# pcb.net
KiCad netlist of a schematic drawn in EAGLE
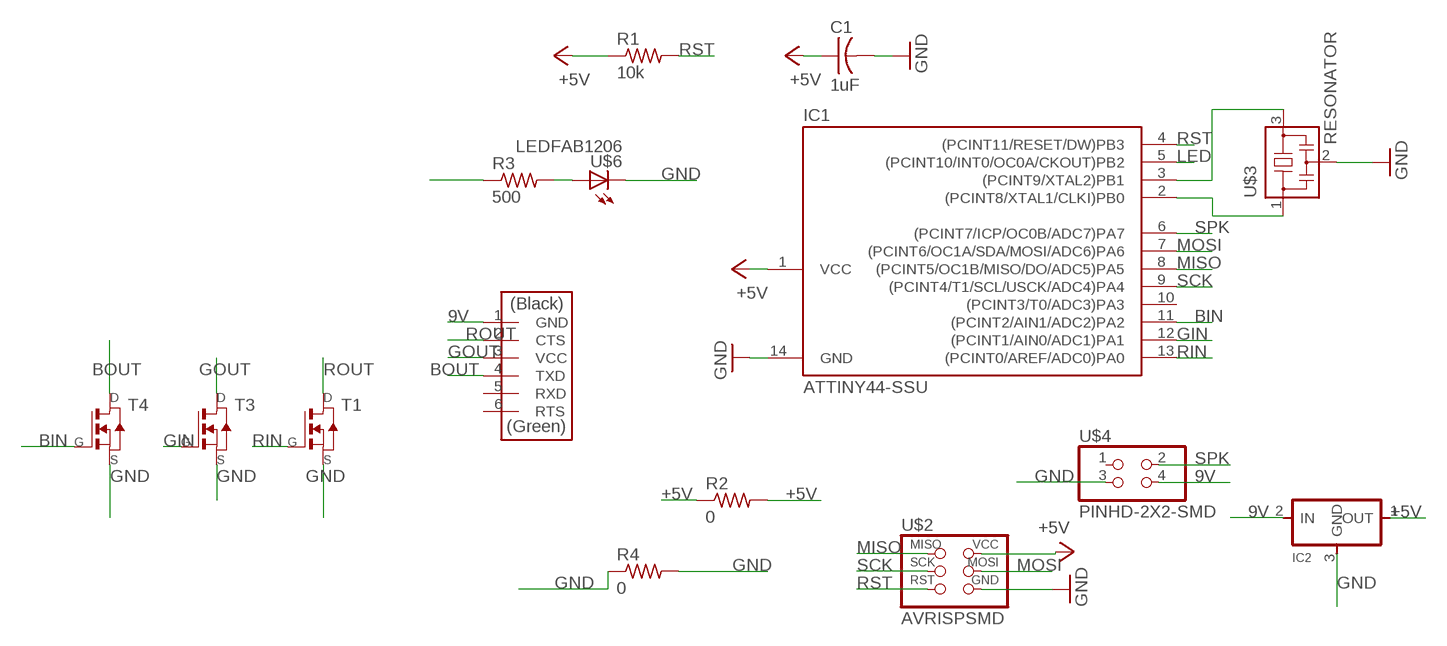
[diagram p0: schematic, sheet 1]

(export (version "E")
  (design (tool "Eeschema 10.0.6"))
  (components
    (comp (ref "C1")
      (value "1uF")
      (footprint "eagle-import:C1206FAB")
      (libsource (lib "eagle-import") (part "CAP-US1206FAB"))
    )
    (comp (ref "IC1")
      (value "ATTINY44-SSU")
      (footprint "eagle-import:SOIC14")
      (libsource (lib "eagle-import") (part "ATTINY44-SSU"))
    )
    (comp (ref "IC2")
      (value "REGULATORSOT23")
      (footprint "eagle-import:SOT23")
      (libsource (lib "eagle-import") (part "REGULATORSOT23"))
    )
    (comp (ref "R1")
      (value "10k")
      (footprint "eagle-import:R1206FAB")
      (libsource (lib "eagle-import") (part "RES-US1206FAB"))
    )
    (comp (ref "R2")
      (value "0")
      (footprint "eagle-import:R1206FAB")
      (libsource (lib "eagle-import") (part "RES-US1206FAB"))
    )
    (comp (ref "R3")
      (value "500")
      (footprint "eagle-import:R1206FAB")
      (libsource (lib "eagle-import") (part "RES-US1206FAB"))
    )
    (comp (ref "R4")
      (value "0")
      (footprint "eagle-import:R1206FAB")
      (libsource (lib "eagle-import") (part "RES-US1206FAB"))
    )
    (comp (ref "T1")
      (value "NMOSFETSOT23")
      (footprint "eagle-import:SOT-23")
      (libsource (lib "eagle-import") (part "NMOSFETSOT23"))
    )
    (comp (ref "T3")
      (value "NMOSFETSOT23")
      (footprint "eagle-import:SOT-23")
      (libsource (lib "eagle-import") (part "NMOSFETSOT23"))
    )
    (comp (ref "T4")
      (value "NMOSFETSOT23")
      (footprint "eagle-import:SOT-23")
      (libsource (lib "eagle-import") (part "NMOSFETSOT23"))
    )
    (comp (ref "U$1")
      (value "FTDI-SMD-HEADER")
      (footprint "eagle-import:1X06SMD")
      (libsource (lib "eagle-import") (part "FTDI-SMD-HEADER"))
    )
    (comp (ref "U$2")
      (value "AVRISPSMD")
      (footprint "eagle-import:2X03SMD")
      (libsource (lib "eagle-import") (part "AVRISPSMD"))
    )
    (comp (ref "U$3")
      (value "RESONATOR")
      (footprint "eagle-import:EFOBM")
      (libsource (lib "eagle-import") (part "RESONATOR"))
    )
    (comp (ref "U$4")
      (value "PINHD-2X2-SMD")
      (footprint "eagle-import:2X02SMD")
      (libsource (lib "eagle-import") (part "PINHD-2X2-SMD"))
    )
    (comp (ref "U$6")
      (value "LEDFAB1206")
      (footprint "eagle-import:LED1206FAB")
      (libsource (lib "eagle-import") (part "LEDFAB1206"))
    )
  )
  (nets
    (net (code "1") (name "+5V") (class "Default")
      (node (ref "C1") (pin "1") (pinfunction "1_1") (pintype "passive"))
      (node (ref "IC1") (pin "1") (pinfunction "VCC_1") (pintype "power_in"))
      (node (ref "IC2") (pin "1") (pinfunction "OUT_1") (pintype "bidirectional"))
      (node (ref "R1") (pin "1") (pinfunction "1_1") (pintype "passive"))
      (node (ref "R2") (pin "1") (pinfunction "1_1") (pintype "passive"))
      (node (ref "R2") (pin "2") (pinfunction "2_2") (pintype "passive"))
      (node (ref "U$2") (pin "2") (pinfunction "VCC_2") (pintype "passive"))
    )
    (net (code "2") (name "/9V") (class "Default")
      (node (ref "IC2") (pin "2") (pinfunction "IN_2") (pintype "bidirectional"))
      (node (ref "U$1") (pin "1") (pinfunction "GND_1") (pintype "bidirectional"))
      (node (ref "U$4") (pin "4") (pinfunction "4_4") (pintype "passive"))
    )
    (net (code "3") (name "/BIN") (class "Default")
      (node (ref "IC1") (pin "11") (pinfunction "(PCINT2/AIN1/ADC2)PA2_11") (pintype "bidirectional"))
      (node (ref "T4") (pin "3") (pinfunction "G_3") (pintype "passive"))
    )
    (net (code "4") (name "/BOUT") (class "Default")
      (node (ref "T4") (pin "1") (pinfunction "D_1") (pintype "passive"))
      (node (ref "U$1") (pin "4") (pinfunction "TXD_4") (pintype "bidirectional"))
    )
    (net (code "5") (name "/GIN") (class "Default")
      (node (ref "IC1") (pin "12") (pinfunction "(PCINT1/AIN0/ADC1)PA1_12") (pintype "bidirectional"))
      (node (ref "T3") (pin "3") (pinfunction "G_3") (pintype "passive"))
    )
    (net (code "6") (name "/GOUT") (class "Default")
      (node (ref "T3") (pin "1") (pinfunction "D_1") (pintype "passive"))
      (node (ref "U$1") (pin "3") (pinfunction "VCC_3") (pintype "bidirectional"))
    )
    (net (code "7") (name "/LED") (class "Default")
      (node (ref "IC1") (pin "5") (pinfunction "(PCINT10/INT0/OC0A/CKOUT)PB2_5") (pintype "bidirectional"))
      (node (ref "R3") (pin "1") (pinfunction "1_1") (pintype "passive"))
    )
    (net (code "8") (name "/MISO") (class "Default")
      (node (ref "IC1") (pin "8") (pinfunction "(PCINT5/OC1B/MISO/DO/ADC5)PA5_8") (pintype "bidirectional"))
      (node (ref "U$2") (pin "1") (pinfunction "MISO_1") (pintype "passive"))
    )
    (net (code "9") (name "/MOSI") (class "Default")
      (node (ref "IC1") (pin "7") (pinfunction "(PCINT6/OC1A/SDA/MOSI/ADC6)PA6_7") (pintype "bidirectional"))
      (node (ref "U$2") (pin "4") (pinfunction "MOSI_4") (pintype "passive"))
    )
    (net (code "10") (name "/RIN") (class "Default")
      (node (ref "IC1") (pin "13") (pinfunction "(PCINT0/AREF/ADC0)PA0_13") (pintype "bidirectional"))
      (node (ref "T1") (pin "3") (pinfunction "G_3") (pintype "passive"))
    )
    (net (code "11") (name "/ROUT") (class "Default")
      (node (ref "T1") (pin "1") (pinfunction "D_1") (pintype "passive"))
      (node (ref "U$1") (pin "2") (pinfunction "CTS_2") (pintype "bidirectional"))
    )
    (net (code "12") (name "/RST") (class "Default")
      (node (ref "IC1") (pin "4") (pinfunction "(PCINT11/RESET/DW)PB3_4") (pintype "bidirectional"))
      (node (ref "R1") (pin "2") (pinfunction "2_2") (pintype "passive"))
      (node (ref "U$2") (pin "5") (pinfunction "RST_5") (pintype "passive"))
    )
    (net (code "13") (name "/SCK") (class "Default")
      (node (ref "IC1") (pin "9") (pinfunction "(PCINT4/T1/SCL/USCK/ADC4)PA4_9") (pintype "bidirectional"))
      (node (ref "U$2") (pin "3") (pinfunction "SCK_3") (pintype "passive"))
    )
    (net (code "14") (name "/SPK") (class "Default")
      (node (ref "IC1") (pin "6") (pinfunction "(PCINT7/ICP/OC0B/ADC7)PA7_6") (pintype "bidirectional"))
      (node (ref "U$4") (pin "2") (pinfunction "2_2") (pintype "passive"))
    )
    (net (code "15") (name "GND") (class "Default")
      (node (ref "C1") (pin "2") (pinfunction "2_2") (pintype "passive"))
      (node (ref "IC1") (pin "14") (pinfunction "GND_14") (pintype "power_in"))
      (node (ref "IC2") (pin "3") (pinfunction "GND_3") (pintype "bidirectional"))
      (node (ref "R4") (pin "1") (pinfunction "1_1") (pintype "passive"))
      (node (ref "R4") (pin "2") (pinfunction "2_2") (pintype "passive"))
      (node (ref "T1") (pin "2") (pinfunction "S_2") (pintype "passive"))
      (node (ref "T3") (pin "2") (pinfunction "S_2") (pintype "passive"))
      (node (ref "T4") (pin "2") (pinfunction "S_2") (pintype "passive"))
      (node (ref "U$2") (pin "6") (pinfunction "GND_6") (pintype "passive"))
      (node (ref "U$3") (pin "2") (pinfunction "2_2") (pintype "passive"))
      (node (ref "U$4") (pin "3") (pinfunction "3_3") (pintype "passive"))
      (node (ref "U$6") (pin "2") (pinfunction "C_2") (pintype "passive"))
    )
    (net (code "16") (name "Net-(IC1-(PCINT8{slash}XTAL1{slash}CLKI)PB0)") (class "Default")
      (node (ref "IC1") (pin "2") (pinfunction "(PCINT8/XTAL1/CLKI)PB0_2") (pintype "bidirectional"))
      (node (ref "U$3") (pin "1") (pinfunction "1_1") (pintype "passive"))
    )
    (net (code "17") (name "Net-(IC1-(PCINT9{slash}XTAL2)PB1)") (class "Default")
      (node (ref "IC1") (pin "3") (pinfunction "(PCINT9/XTAL2)PB1_3") (pintype "bidirectional"))
      (node (ref "U$3") (pin "3") (pinfunction "3_3") (pintype "passive"))
    )
    (net (code "18") (name "Net-(U$6-A)") (class "Default")
      (node (ref "R3") (pin "2") (pinfunction "2_2") (pintype "passive"))
      (node (ref "U$6") (pin "1") (pinfunction "A_1") (pintype "passive"))
    )
    (net (code "19") (name "unconnected-(IC1-(PCINT3{slash}T0{slash}ADC3)PA3-Pad10)") (class "Default")
      (node (ref "IC1") (pin "10") (pinfunction "(PCINT3/T0/ADC3)PA3_10") (pintype "bidirectional"))
    )
    (net (code "20") (name "unconnected-(U$1-RTS-Pad6)") (class "Default")
      (node (ref "U$1") (pin "6") (pinfunction "RTS_6") (pintype "bidirectional"))
    )
    (net (code "21") (name "unconnected-(U$1-RXD-Pad5)") (class "Default")
      (node (ref "U$1") (pin "5") (pinfunction "RXD_5") (pintype "bidirectional"))
    )
    (net (code "22") (name "unconnected-(U$4-Pad1)") (class "Default")
      (node (ref "U$4") (pin "1") (pinfunction "1_1") (pintype "passive"))
    )
  )
)
